# poly-lamp-V1_0.net
KiCad netlist of a schematic drawn in EAGLE
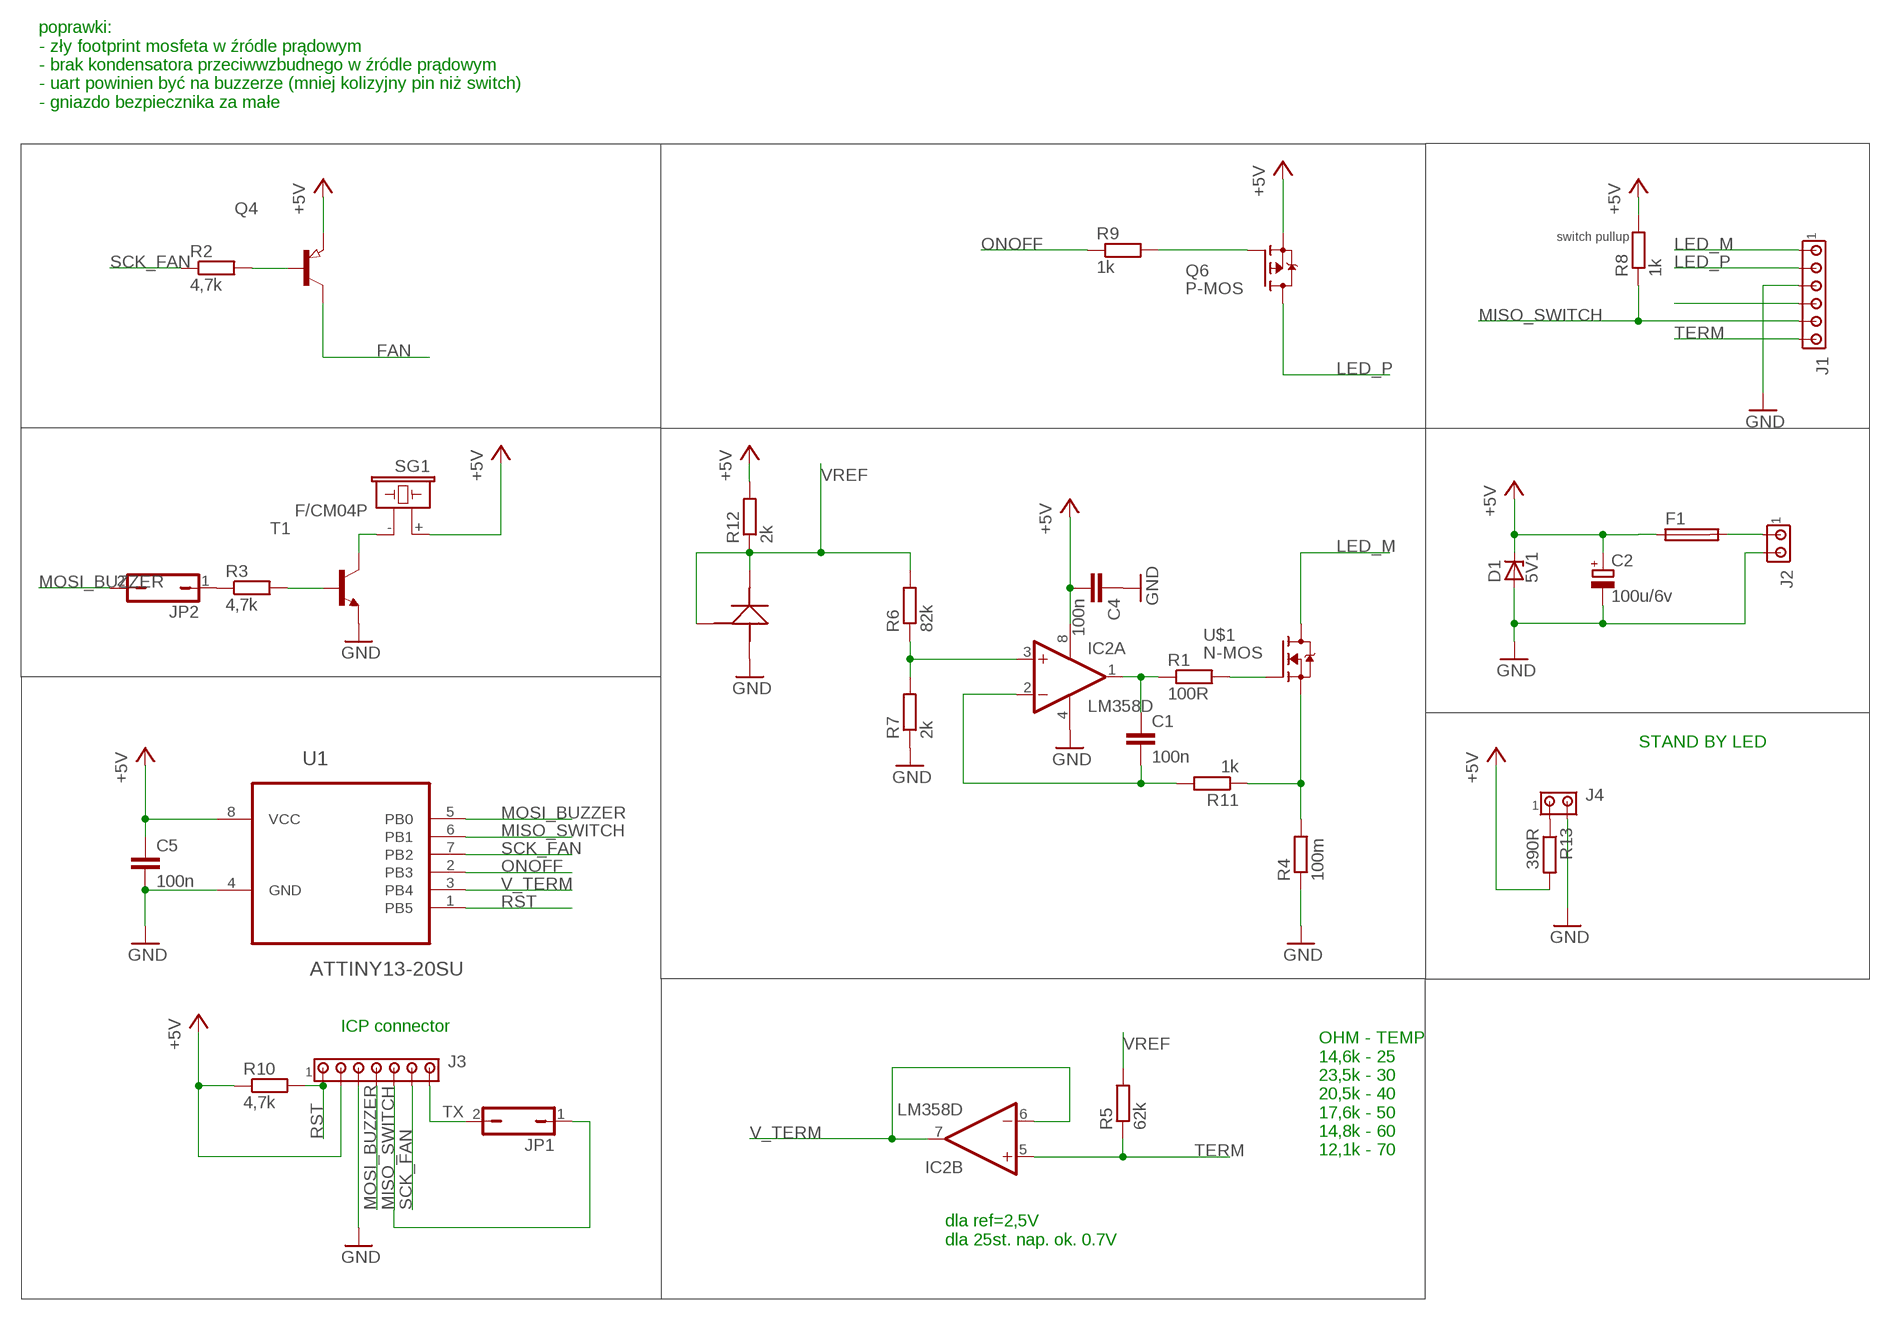
[diagram p0: schematic, sheet 1]

(export (version "E")
  (design (tool "Eeschema 10.0.6"))
  (components
    (comp (ref "C1")
      (value "100n")
      (footprint "eagle-import:C0805")
      (libsource (lib "eagle-import") (part "C-EUC0805"))
    )
    (comp (ref "C2")
      (value "100u/6v")
      (footprint "eagle-import:E2,5-7")
      (libsource (lib "eagle-import") (part "CPOL-EUE2.5-7"))
    )
    (comp (ref "C4")
      (value "100n")
      (footprint "eagle-import:C0805")
      (libsource (lib "eagle-import") (part "C-EUC0805"))
    )
    (comp (ref "C5")
      (value "100n")
      (footprint "eagle-import:C0805")
      (libsource (lib "eagle-import") (part "C-EUC0805"))
    )
    (comp (ref "D1")
      (value "5V1")
      (footprint "eagle-import:DO35Z10")
      (libsource (lib "eagle-import") (part "ZENER-DIODEDO35Z10"))
    )
    (comp (ref "F1")
      (value "SH22,5")
      (footprint "eagle-import:SH22,5")
      (fields (field (name "MF") "SCHURTER") (field (name "MPN") "0031.8201"))
      (libsource (lib "eagle-import") (part "SH22,5"))
    )
    (comp (ref "IC2")
      (value "LM358D")
      (footprint "eagle-import:SO08")
      (libsource (lib "eagle-import") (part "LM358D"))
    )
    (comp (ref "J1")
      (value "MTA06-100")
      (footprint "eagle-import:10X06MTA")
      (libsource (lib "eagle-import") (part "MTA06-100"))
    )
    (comp (ref "J2")
      (value "MTA02-100")
      (footprint "eagle-import:10X02MTA")
      (libsource (lib "eagle-import") (part "MTA02-100"))
    )
    (comp (ref "J3")
      (value "MTA07-100")
      (footprint "eagle-import:10X07MTA")
      (libsource (lib "eagle-import") (part "MTA07-100"))
    )
    (comp (ref "J4")
      (value "MTA02-100")
      (footprint "eagle-import:10X02MTA")
      (libsource (lib "eagle-import") (part "MTA02-100"))
    )
    (comp (ref "JP1")
      (value "JP1Q")
      (footprint "eagle-import:JP1")
      (libsource (lib "eagle-import") (part "JP1Q"))
    )
    (comp (ref "JP2")
      (value "JP1Q")
      (footprint "eagle-import:JP1")
      (libsource (lib "eagle-import") (part "JP1Q"))
    )
    (comp (ref "Q4")
      (value "PNP-TRANSISTOR_SOT23")
      (footprint "eagle-import:SOT23")
      (libsource (lib "eagle-import") (part "PNP-TRANSISTOR_SOT23"))
    )
    (comp (ref "Q6")
      (value "P-MOS")
      (footprint "eagle-import:TO252")
      (libsource (lib "eagle-import") (part "FDD4141TO252"))
    )
    (comp (ref "R1")
      (value "100R")
      (footprint "eagle-import:R0805")
      (libsource (lib "eagle-import") (part "R-EU_R0805"))
    )
    (comp (ref "R2")
      (value "4,7k")
      (footprint "eagle-import:R0805")
      (libsource (lib "eagle-import") (part "resistor_R-EU_R0805"))
    )
    (comp (ref "R3")
      (value "4,7k")
      (footprint "eagle-import:R0805")
      (libsource (lib "eagle-import") (part "resistor_R-EU_R0805"))
    )
    (comp (ref "R4")
      (value "100m")
      (footprint "eagle-import:R0805")
      (libsource (lib "eagle-import") (part "R-EU_R0805"))
    )
    (comp (ref "R5")
      (value "62k")
      (footprint "eagle-import:R0805")
      (libsource (lib "eagle-import") (part "resistor_R-EU_R0805"))
    )
    (comp (ref "R6")
      (value "82k")
      (footprint "eagle-import:R0805")
      (libsource (lib "eagle-import") (part "R-EU_R0805"))
    )
    (comp (ref "R7")
      (value "2k")
      (footprint "eagle-import:R0805")
      (libsource (lib "eagle-import") (part "R-EU_R0805"))
    )
    (comp (ref "R8")
      (value "1k")
      (footprint "eagle-import:R0805")
      (libsource (lib "eagle-import") (part "R-EU_R0805"))
    )
    (comp (ref "R9")
      (value "1k")
      (footprint "eagle-import:R0805")
      (libsource (lib "eagle-import") (part "R-EU_R0805"))
    )
    (comp (ref "R10")
      (value "4,7k")
      (footprint "eagle-import:R0805")
      (libsource (lib "eagle-import") (part "R-EU_R0805"))
    )
    (comp (ref "R11")
      (value "1k")
      (footprint "eagle-import:R0805")
      (libsource (lib "eagle-import") (part "R-EU_R0805"))
    )
    (comp (ref "R12")
      (value "2k")
      (footprint "eagle-import:R0805")
      (libsource (lib "eagle-import") (part "R-EU_R0805"))
    )
    (comp (ref "R13")
      (value "390R")
      (footprint "eagle-import:R0805")
      (libsource (lib "eagle-import") (part "R-EU_R0805"))
    )
    (comp (ref "SG1")
      (value "F/CM04P")
      (footprint "eagle-import:F_CM04P")
      (libsource (lib "eagle-import") (part "F/CM04P"))
    )
    (comp (ref "T1")
      (value "BC817-16-NPN-SOT23-BEC")
      (footprint "eagle-import:SOT23-BEC")
      (libsource (lib "eagle-import") (part "-NPN-SOT23-BECBC817-16"))
    )
    (comp (ref "U$1")
      (value "N-MOS")
      (footprint "eagle-import:TO252")
      (libsource (lib "eagle-import") (part "N-MOS"))
    )
    (comp (ref "U$2")
      (value "TL431")
      (footprint "eagle-import:SOT23-BEC")
      (libsource (lib "eagle-import") (part "TL431"))
    )
    (comp (ref "U1")
      (value "ATTINY13-20SU")
      (footprint "eagle-import:SOIC127P798X216-8N")
      (libsource (lib "eagle-import") (part "ATTINY13-20SU"))
    )
  )
  (nets
    (net (code "1") (name "+5V") (class "Default")
      (node (ref "C2") (pin "+") (pinfunction "+_+") (pintype "passive"))
      (node (ref "C4") (pin "2") (pinfunction "2_2") (pintype "passive"))
      (node (ref "C5") (pin "1") (pinfunction "1_1") (pintype "passive"))
      (node (ref "D1") (pin "C") (pinfunction "C_C") (pintype "passive"))
      (node (ref "F1") (pin "1") (pinfunction "1_1") (pintype "passive"))
      (node (ref "IC2") (pin "8") (pinfunction "V+_8") (pintype "power_in"))
      (node (ref "J3") (pin "2") (pinfunction "2_2") (pintype "passive"))
      (node (ref "Q4") (pin "2") (pinfunction "E_2") (pintype "passive"))
      (node (ref "Q6") (pin "2") (pinfunction "S_2") (pintype "passive"))
      (node (ref "R10") (pin "1") (pinfunction "1_1") (pintype "passive"))
      (node (ref "R12") (pin "2") (pinfunction "2_2") (pintype "passive"))
      (node (ref "R13") (pin "2") (pinfunction "2_2") (pintype "passive"))
      (node (ref "R8") (pin "2") (pinfunction "2_2") (pintype "passive"))
      (node (ref "SG1") (pin "+") (pinfunction "1_+") (pintype "passive"))
      (node (ref "U1") (pin "8") (pinfunction "VCC_8") (pintype "power_in"))
    )
    (net (code "2") (name "/FAN") (class "Default")
      (node (ref "J1") (pin "4") (pinfunction "4_4") (pintype "passive"))
      (node (ref "Q4") (pin "3") (pinfunction "C_3") (pintype "passive"))
    )
    (net (code "3") (name "/LED_M") (class "Default")
      (node (ref "J1") (pin "1") (pinfunction "1_1") (pintype "passive"))
      (node (ref "U$1") (pin "3") (pinfunction "D_3") (pintype "passive"))
    )
    (net (code "4") (name "/LED_P") (class "Default")
      (node (ref "J1") (pin "2") (pinfunction "2_2") (pintype "passive"))
      (node (ref "Q6") (pin "3") (pinfunction "D_3") (pintype "passive"))
    )
    (net (code "5") (name "/MISO_SWITCH") (class "Default")
      (node (ref "J1") (pin "5") (pinfunction "5_5") (pintype "passive"))
      (node (ref "J3") (pin "5") (pinfunction "5_5") (pintype "passive"))
      (node (ref "JP1") (pin "1") (pinfunction "1_1") (pintype "passive"))
      (node (ref "R8") (pin "1") (pinfunction "1_1") (pintype "passive"))
      (node (ref "U1") (pin "6") (pinfunction "PB1_6") (pintype "bidirectional"))
    )
    (net (code "6") (name "/MOSI_BUZZER") (class "Default")
      (node (ref "J3") (pin "4") (pinfunction "4_4") (pintype "passive"))
      (node (ref "JP2") (pin "2") (pinfunction "2_2") (pintype "passive"))
      (node (ref "U1") (pin "5") (pinfunction "PB0_5") (pintype "bidirectional"))
    )
    (net (code "7") (name "/ONOFF") (class "Default")
      (node (ref "R9") (pin "1") (pinfunction "1_1") (pintype "passive"))
      (node (ref "U1") (pin "2") (pinfunction "PB3_2") (pintype "bidirectional"))
    )
    (net (code "8") (name "/RST") (class "Default")
      (node (ref "J3") (pin "1") (pinfunction "1_1") (pintype "passive"))
      (node (ref "R10") (pin "2") (pinfunction "2_2") (pintype "passive"))
      (node (ref "U1") (pin "1") (pinfunction "PB5_1") (pintype "bidirectional"))
    )
    (net (code "9") (name "/SCK_FAN") (class "Default")
      (node (ref "J3") (pin "6") (pinfunction "6_6") (pintype "passive"))
      (node (ref "R2") (pin "1") (pinfunction "1_1") (pintype "passive"))
      (node (ref "U1") (pin "7") (pinfunction "PB2_7") (pintype "bidirectional"))
    )
    (net (code "10") (name "/TERM") (class "Default")
      (node (ref "IC2") (pin "5") (pinfunction "+IN_5") (pintype "input"))
      (node (ref "J1") (pin "6") (pinfunction "6_6") (pintype "passive"))
      (node (ref "R5") (pin "1") (pinfunction "1_1") (pintype "passive"))
    )
    (net (code "11") (name "/TX") (class "Default")
      (node (ref "J3") (pin "7") (pinfunction "7_7") (pintype "passive"))
      (node (ref "JP1") (pin "2") (pinfunction "2_2") (pintype "passive"))
    )
    (net (code "12") (name "/VREF") (class "Default")
      (node (ref "R12") (pin "1") (pinfunction "1_1") (pintype "passive"))
      (node (ref "R5") (pin "2") (pinfunction "2_2") (pintype "passive"))
      (node (ref "R6") (pin "2") (pinfunction "2_2") (pintype "passive"))
      (node (ref "U$2") (pin "B") (pinfunction "K_B") (pintype "bidirectional"))
      (node (ref "U$2") (pin "E") (pinfunction "R_E") (pintype "bidirectional"))
    )
    (net (code "13") (name "/V_TERM") (class "Default")
      (node (ref "IC2") (pin "6") (pinfunction "-IN_6") (pintype "input"))
      (node (ref "IC2") (pin "7") (pinfunction "OUT_7") (pintype "output"))
      (node (ref "U1") (pin "3") (pinfunction "PB4_3") (pintype "bidirectional"))
    )
    (net (code "14") (name "GND") (class "Default")
      (node (ref "C2") (pin "-") (pinfunction "-_-") (pintype "passive"))
      (node (ref "C4") (pin "1") (pinfunction "1_1") (pintype "passive"))
      (node (ref "C5") (pin "2") (pinfunction "2_2") (pintype "passive"))
      (node (ref "D1") (pin "A") (pinfunction "A_A") (pintype "passive"))
      (node (ref "IC2") (pin "4") (pinfunction "V-_4") (pintype "power_in"))
      (node (ref "J1") (pin "3") (pinfunction "3_3") (pintype "passive"))
      (node (ref "J2") (pin "2") (pinfunction "2_2") (pintype "passive"))
      (node (ref "J3") (pin "3") (pinfunction "3_3") (pintype "passive"))
      (node (ref "J4") (pin "2") (pinfunction "2_2") (pintype "passive"))
      (node (ref "R4") (pin "1") (pinfunction "1_1") (pintype "passive"))
      (node (ref "R7") (pin "1") (pinfunction "1_1") (pintype "passive"))
      (node (ref "T1") (pin "E") (pinfunction "E_E") (pintype "passive"))
      (node (ref "U$2") (pin "C") (pinfunction "A_C") (pintype "bidirectional"))
      (node (ref "U1") (pin "4") (pinfunction "GND_4") (pintype "passive"))
    )
    (net (code "15") (name "Net-(F1-Pad2)") (class "Default")
      (node (ref "F1") (pin "2") (pinfunction "2_2") (pintype "passive"))
      (node (ref "J2") (pin "1") (pinfunction "1_1") (pintype "passive"))
    )
    (net (code "16") (name "Net-(IC2A-+IN)") (class "Default")
      (node (ref "IC2") (pin "3") (pinfunction "+IN_3") (pintype "input"))
      (node (ref "R6") (pin "1") (pinfunction "1_1") (pintype "passive"))
      (node (ref "R7") (pin "2") (pinfunction "2_2") (pintype "passive"))
    )
    (net (code "17") (name "Net-(IC2A--IN)") (class "Default")
      (node (ref "C1") (pin "2") (pinfunction "2_2") (pintype "passive"))
      (node (ref "IC2") (pin "2") (pinfunction "-IN_2") (pintype "input"))
      (node (ref "R11") (pin "2") (pinfunction "2_2") (pintype "passive"))
    )
    (net (code "18") (name "Net-(IC2A-OUT)") (class "Default")
      (node (ref "C1") (pin "1") (pinfunction "1_1") (pintype "passive"))
      (node (ref "IC2") (pin "1") (pinfunction "OUT_1") (pintype "output"))
      (node (ref "R1") (pin "1") (pinfunction "1_1") (pintype "passive"))
    )
    (net (code "19") (name "Net-(J4-Pad1)") (class "Default")
      (node (ref "J4") (pin "1") (pinfunction "1_1") (pintype "passive"))
      (node (ref "R13") (pin "1") (pinfunction "1_1") (pintype "passive"))
    )
    (net (code "20") (name "Net-(JP2-Pad1)") (class "Default")
      (node (ref "JP2") (pin "1") (pinfunction "1_1") (pintype "passive"))
      (node (ref "R3") (pin "1") (pinfunction "1_1") (pintype "passive"))
    )
    (net (code "21") (name "Net-(Q4-B)") (class "Default")
      (node (ref "Q4") (pin "1") (pinfunction "B_1") (pintype "passive"))
      (node (ref "R2") (pin "2") (pinfunction "2_2") (pintype "passive"))
    )
    (net (code "22") (name "Net-(Q6-G)") (class "Default")
      (node (ref "Q6") (pin "1") (pinfunction "G_1") (pintype "passive"))
      (node (ref "R9") (pin "2") (pinfunction "2_2") (pintype "passive"))
    )
    (net (code "23") (name "Net-(R3-Pad2)") (class "Default")
      (node (ref "R3") (pin "2") (pinfunction "2_2") (pintype "passive"))
      (node (ref "T1") (pin "B") (pinfunction "B_B") (pintype "passive"))
    )
    (net (code "24") (name "Net-(SG1-2)") (class "Default")
      (node (ref "SG1") (pin "-") (pinfunction "2_-") (pintype "passive"))
      (node (ref "T1") (pin "C") (pinfunction "C_C") (pintype "passive"))
    )
    (net (code "25") (name "Net-(U$1-G)") (class "Default")
      (node (ref "R1") (pin "2") (pinfunction "2_2") (pintype "passive"))
      (node (ref "U$1") (pin "1") (pinfunction "G_1") (pintype "passive"))
    )
    (net (code "26") (name "Net-(U$1-S)") (class "Default")
      (node (ref "R11") (pin "1") (pinfunction "1_1") (pintype "passive"))
      (node (ref "R4") (pin "2") (pinfunction "2_2") (pintype "passive"))
      (node (ref "U$1") (pin "2") (pinfunction "S_2") (pintype "passive"))
    )
  )
)
